# CAN-FD_Shield.net
KiCad netlist of a schematic drawn in EAGLE
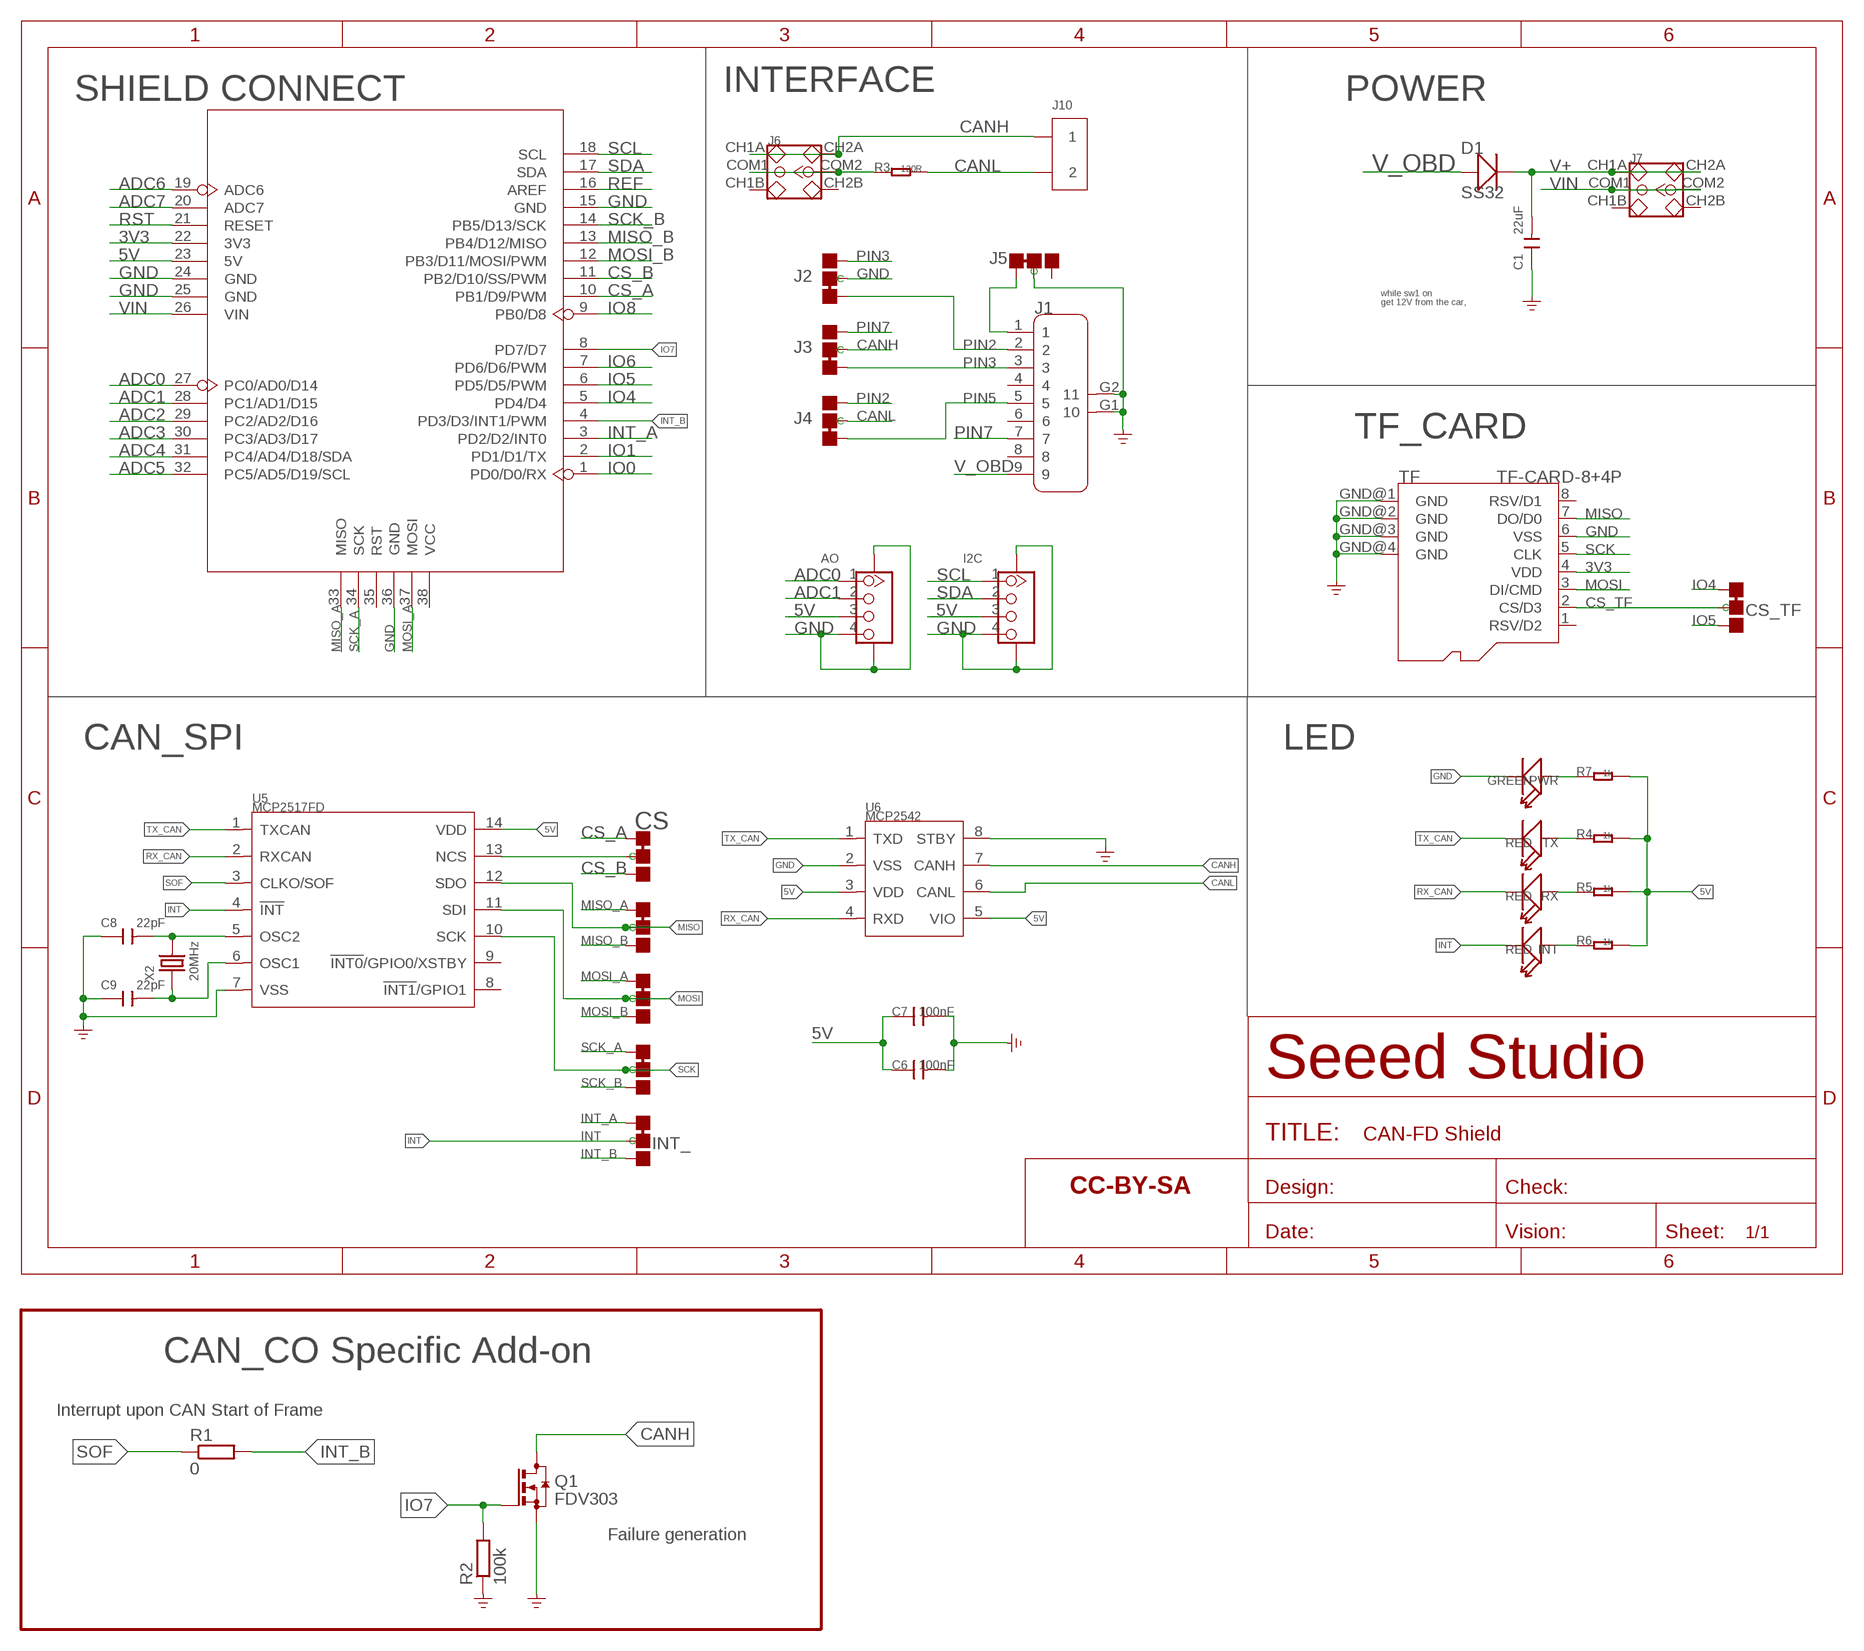
[diagram p0: schematic, sheet 1]

(export (version "E")
  (design (tool "Eeschema 10.0.6"))
  (components
    (comp (ref "AO")
      (value "GROVE-CONNECTOR-SMD'90D'")
      (footprint "eagle-import:HW4-SMD-2.0-90D")
      (libsource (lib "eagle-import") (part "GROVE-CONNECTOR-SMD'90D'"))
    )
    (comp (ref "C1")
      (value "22uF")
      (footprint "eagle-import:C1206")
      (libsource (lib "eagle-import") (part "CAP-1206"))
    )
    (comp (ref "C6")
      (value "100nF")
      (footprint "eagle-import:0603")
      (libsource (lib "eagle-import") (part "C-0603"))
    )
    (comp (ref "C7")
      (value "100nF")
      (footprint "eagle-import:0603")
      (libsource (lib "eagle-import") (part "C-0603"))
    )
    (comp (ref "C8")
      (value "22pF")
      (footprint "eagle-import:C0603")
      (libsource (lib "eagle-import") (part "CAP-0603"))
    )
    (comp (ref "C9")
      (value "22pF")
      (footprint "eagle-import:C0603")
      (libsource (lib "eagle-import") (part "CAP-0603"))
    )
    (comp (ref "CS")
      (value "JUMPER-3P-SHORT")
      (footprint "eagle-import:3P-SMD-SHORT")
      (libsource (lib "eagle-import") (part "JUMPER-3P-SHORT"))
    )
    (comp (ref "CS_TF")
      (value "JUMPER-3P-SHORT")
      (footprint "eagle-import:3P-SMD-SHORT")
      (libsource (lib "eagle-import") (part "JUMPER-3P-SHORT"))
    )
    (comp (ref "D1")
      (value "SS32")
      (footprint "eagle-import:D2010")
      (libsource (lib "eagle-import") (part "D-SMA"))
    )
    (comp (ref "I2C")
      (value "GROVE-CONNECTOR-SMD'90D'")
      (footprint "eagle-import:HW4-SMD-2.0-90D")
      (libsource (lib "eagle-import") (part "GROVE-CONNECTOR-SMD'90D'"))
    )
    (comp (ref "INT")
      (value "RED")
      (footprint "eagle-import:LED-0603")
      (libsource (lib "eagle-import") (part "LED'0603'"))
    )
    (comp (ref "INT_")
      (value "JUMPER-3P-SHORT")
      (footprint "eagle-import:3P-SMD-SHORT")
      (libsource (lib "eagle-import") (part "JUMPER-3P-SHORT"))
    )
    (comp (ref "J1")
      (value "DB9'MEAL'")
      (footprint "eagle-import:DB9-MEAL")
      (libsource (lib "eagle-import") (part "DB9'MEAL'"))
    )
    (comp (ref "J2")
      (value "JUMPER-3P-SHORT")
      (footprint "eagle-import:3P-SMD-SHORT")
      (libsource (lib "eagle-import") (part "JUMPER-3P-SHORT"))
    )
    (comp (ref "J3")
      (value "JUMPER-3P-SHORT")
      (footprint "eagle-import:3P-SMD-SHORT")
      (libsource (lib "eagle-import") (part "JUMPER-3P-SHORT"))
    )
    (comp (ref "J4")
      (value "JUMPER-3P-SHORT")
      (footprint "eagle-import:3P-SMD-SHORT")
      (libsource (lib "eagle-import") (part "JUMPER-3P-SHORT"))
    )
    (comp (ref "J5")
      (value "JUMPER-3P-SHORT")
      (footprint "eagle-import:3P-SMD-SHORT")
      (libsource (lib "eagle-import") (part "JUMPER-3P-SHORT"))
    )
    (comp (ref "J6")
      (value "SWITCH-2CH-6P")
      (footprint "eagle-import:6P-2CH-2.54-7.6X3.0")
      (libsource (lib "eagle-import") (part "SWITCH-2CH-6P"))
    )
    (comp (ref "J7")
      (value "SWITCH-2CH-6P")
      (footprint "eagle-import:6P-2CH-2.54-7.6X3.0")
      (libsource (lib "eagle-import") (part "SWITCH-2CH-6P"))
    )
    (comp (ref "J10")
      (value "SCREW-TERMINAL-2P'5.08'")
      (footprint "eagle-import:H2-5.0-10.5X8.0MM")
      (libsource (lib "eagle-import") (part "SCREW-TERMINAL-2P'5.08'"))
    )
    (comp (ref "MISO")
      (value "JUMPER-3P-SHORT")
      (footprint "eagle-import:3P-SMD-SHORT")
      (libsource (lib "eagle-import") (part "JUMPER-3P-SHORT"))
    )
    (comp (ref "MOSI")
      (value "JUMPER-3P-SHORT")
      (footprint "eagle-import:3P-SMD-SHORT")
      (libsource (lib "eagle-import") (part "JUMPER-3P-SHORT"))
    )
    (comp (ref "PWR")
      (value "GREEN")
      (footprint "eagle-import:LED-0603")
      (libsource (lib "eagle-import") (part "LED'0603'"))
    )
    (comp (ref "Q1")
      (value "FDV303")
      (footprint "eagle-import:SOT23")
      (libsource (lib "eagle-import") (part "BSS123"))
    )
    (comp (ref "R1")
      (value "0")
      (footprint "eagle-import:R0603")
      (libsource (lib "eagle-import") (part "R-EU_R0603"))
    )
    (comp (ref "R2")
      (value "100k")
      (footprint "eagle-import:R0603")
      (libsource (lib "eagle-import") (part "R-EU_R0603"))
    )
    (comp (ref "R3")
      (value "120R")
      (footprint "eagle-import:0603")
      (libsource (lib "eagle-import") (part "R-0603"))
    )
    (comp (ref "R4")
      (value "1k")
      (footprint "eagle-import:0603")
      (libsource (lib "eagle-import") (part "R-0603"))
    )
    (comp (ref "R5")
      (value "1k")
      (footprint "eagle-import:0603")
      (libsource (lib "eagle-import") (part "R-0603"))
    )
    (comp (ref "R6")
      (value "1k")
      (footprint "eagle-import:0603")
      (libsource (lib "eagle-import") (part "R-0603"))
    )
    (comp (ref "R7")
      (value "1k")
      (footprint "eagle-import:0603")
      (libsource (lib "eagle-import") (part "R-0603"))
    )
    (comp (ref "RX")
      (value "RED")
      (footprint "eagle-import:LED-0603")
      (libsource (lib "eagle-import") (part "LED'0603'"))
    )
    (comp (ref "SCK")
      (value "JUMPER-3P-SHORT")
      (footprint "eagle-import:3P-SMD-SHORT")
      (libsource (lib "eagle-import") (part "JUMPER-3P-SHORT"))
    )
    (comp (ref "TF")
      (value "TF-CARD-8+4P")
      (footprint "eagle-import:TF-8+4P-1.1-13.5X15MM")
      (libsource (lib "eagle-import") (part "TF-CARD-8+4P"))
    )
    (comp (ref "TX")
      (value "RED")
      (footprint "eagle-import:LED-0603")
      (libsource (lib "eagle-import") (part "LED'0603'"))
    )
    (comp (ref "U$5")
      (value "SEEEDSTUDIO-OPEN-SCH-FRAME")
      (footprint "eagle-import:SEEEDSTUDIO-PCB-FRAME")
      (libsource (lib "eagle-import") (part "SEEEDSTUDIO-OPEN-SCH-FRAME"))
    )
    (comp (ref "U4")
      (value "ARDUINO-38P'WITH/-SILK'")
      (footprint "eagle-import:ARDUINO-38P-WITH_-SILK-500519002")
      (libsource (lib "eagle-import") (part "ARDUINO-38P'WITH/-SILK'"))
    )
    (comp (ref "U5")
      (value "MCP2517FD")
      (footprint "eagle-import:SOIC14-1.27-8.6X3.9MM")
      (libsource (lib "eagle-import") (part "CONTROLLER-MCP2517FD"))
    )
    (comp (ref "U6")
      (value "MCP2542")
      (footprint "eagle-import:SOIC8-1.27-5X4MM")
      (libsource (lib "eagle-import") (part "TRANSCEIVER-MCP2542"))
    )
    (comp (ref "X2")
      (value "20MHz")
      (footprint "eagle-import:HC49US")
      (libsource (lib "eagle-import") (part "CRYSTAL-2P'HC49US'"))
    )
  )
  (nets
    (net (code "1") (name "/3V3") (class "Default")
      (node (ref "TF") (pin "4") (pinfunction "VDD_4") (pintype "bidirectional"))
      (node (ref "U4") (pin "22") (pinfunction "3V3_22") (pintype "bidirectional"))
    )
    (net (code "2") (name "/ADC0") (class "Default")
      (node (ref "AO") (pin "1") (pinfunction "1_1") (pintype "bidirectional"))
      (node (ref "U4") (pin "27") (pinfunction "PC0/AD0/D14_27") (pintype "bidirectional"))
    )
    (net (code "3") (name "/ADC1") (class "Default")
      (node (ref "AO") (pin "2") (pinfunction "2_2") (pintype "bidirectional"))
      (node (ref "U4") (pin "28") (pinfunction "PC1/AD1/D15_28") (pintype "bidirectional"))
    )
    (net (code "4") (name "/ADC2") (class "Default")
      (node (ref "U4") (pin "29") (pinfunction "PC2/AD2/D16_29") (pintype "bidirectional"))
    )
    (net (code "5") (name "/ADC3") (class "Default")
      (node (ref "U4") (pin "30") (pinfunction "PC3/AD3/D17_30") (pintype "bidirectional"))
    )
    (net (code "6") (name "/ADC4") (class "Default")
      (node (ref "U4") (pin "31") (pinfunction "PC4/AD4/D18/SDA_31") (pintype "bidirectional"))
    )
    (net (code "7") (name "/ADC5") (class "Default")
      (node (ref "U4") (pin "32") (pinfunction "PC5/AD5/D19/SCL_32") (pintype "bidirectional"))
    )
    (net (code "8") (name "/ADC6") (class "Default")
      (node (ref "U4") (pin "19") (pinfunction "ADC6_19") (pintype "bidirectional"))
    )
    (net (code "9") (name "/ADC7") (class "Default")
      (node (ref "U4") (pin "20") (pinfunction "ADC7_20") (pintype "bidirectional"))
    )
    (net (code "10") (name "/CS_A") (class "Default")
      (node (ref "CS") (pin "11") (pinfunction "L_11") (pintype "bidirectional"))
      (node (ref "U4") (pin "10") (pinfunction "PB1/D9/PWM_10") (pintype "bidirectional"))
    )
    (net (code "11") (name "/CS_B") (class "Default")
      (node (ref "CS") (pin "00") (pinfunction "R_00") (pintype "bidirectional"))
      (node (ref "U4") (pin "11") (pinfunction "PB2/D10/SS/PWM_11") (pintype "bidirectional"))
    )
    (net (code "12") (name "/CS_TF") (class "Default")
      (node (ref "CS_TF") (pin "MM") (pinfunction "C_MM") (pintype "bidirectional"))
      (node (ref "TF") (pin "2") (pinfunction "CS/D3_2") (pintype "bidirectional"))
    )
    (net (code "13") (name "/INT_A") (class "Default")
      (node (ref "INT_") (pin "11") (pinfunction "L_11") (pintype "bidirectional"))
      (node (ref "U4") (pin "3") (pinfunction "PD2/D2/INT0_3") (pintype "bidirectional"))
    )
    (net (code "14") (name "/IO0") (class "Default")
      (node (ref "U4") (pin "1") (pinfunction "PD0/D0/RX_1") (pintype "bidirectional"))
    )
    (net (code "15") (name "/IO1") (class "Default")
      (node (ref "U4") (pin "2") (pinfunction "PD1/D1/TX_2") (pintype "bidirectional"))
    )
    (net (code "16") (name "/IO4") (class "Default")
      (node (ref "CS_TF") (pin "11") (pinfunction "L_11") (pintype "bidirectional"))
      (node (ref "U4") (pin "5") (pinfunction "PD4/D4_5") (pintype "bidirectional"))
    )
    (net (code "17") (name "/IO5") (class "Default")
      (node (ref "CS_TF") (pin "00") (pinfunction "R_00") (pintype "bidirectional"))
      (node (ref "U4") (pin "6") (pinfunction "PD5/D5/PWM_6") (pintype "bidirectional"))
    )
    (net (code "18") (name "/IO6") (class "Default")
      (node (ref "U4") (pin "7") (pinfunction "PD6/D6/PWM_7") (pintype "bidirectional"))
    )
    (net (code "19") (name "/IO8") (class "Default")
      (node (ref "U4") (pin "9") (pinfunction "PB0/D8_9") (pintype "bidirectional"))
    )
    (net (code "20") (name "/MISO_A") (class "Default")
      (node (ref "MISO") (pin "11") (pinfunction "L_11") (pintype "bidirectional"))
      (node (ref "U4") (pin "33") (pinfunction "MISO_33") (pintype "bidirectional"))
    )
    (net (code "21") (name "/MISO_B") (class "Default")
      (node (ref "MISO") (pin "00") (pinfunction "R_00") (pintype "bidirectional"))
      (node (ref "U4") (pin "13") (pinfunction "PB4/D12/MISO_13") (pintype "bidirectional"))
    )
    (net (code "22") (name "/MOSI_A") (class "Default")
      (node (ref "MOSI") (pin "11") (pinfunction "L_11") (pintype "bidirectional"))
      (node (ref "U4") (pin "37") (pinfunction "MOSI_37") (pintype "bidirectional"))
    )
    (net (code "23") (name "/MOSI_B") (class "Default")
      (node (ref "MOSI") (pin "00") (pinfunction "R_00") (pintype "bidirectional"))
      (node (ref "U4") (pin "12") (pinfunction "PB3/D11/MOSI/PWM_12") (pintype "bidirectional"))
    )
    (net (code "24") (name "/PIN2") (class "Default")
      (node (ref "J1") (pin "2") (pinfunction "2_2") (pintype "bidirectional"))
      (node (ref "J2") (pin "11") (pinfunction "L_11") (pintype "bidirectional"))
      (node (ref "J4") (pin "00") (pinfunction "R_00") (pintype "bidirectional"))
    )
    (net (code "25") (name "/PIN3") (class "Default")
      (node (ref "J1") (pin "3") (pinfunction "3_3") (pintype "bidirectional"))
      (node (ref "J2") (pin "00") (pinfunction "R_00") (pintype "bidirectional"))
      (node (ref "J3") (pin "11") (pinfunction "L_11") (pintype "bidirectional"))
    )
    (net (code "26") (name "/PIN5") (class "Default")
      (node (ref "J1") (pin "5") (pinfunction "5_5") (pintype "bidirectional"))
      (node (ref "J4") (pin "11") (pinfunction "L_11") (pintype "bidirectional"))
    )
    (net (code "27") (name "/PIN7") (class "Default")
      (node (ref "J1") (pin "7") (pinfunction "7_7") (pintype "bidirectional"))
      (node (ref "J3") (pin "00") (pinfunction "R_00") (pintype "bidirectional"))
    )
    (net (code "28") (name "/REF") (class "Default")
      (node (ref "U4") (pin "16") (pinfunction "AREF_16") (pintype "bidirectional"))
    )
    (net (code "29") (name "/RST") (class "Default")
      (node (ref "U4") (pin "21") (pinfunction "RESET_21") (pintype "bidirectional"))
    )
    (net (code "30") (name "/SCK_A") (class "Default")
      (node (ref "SCK") (pin "11") (pinfunction "L_11") (pintype "bidirectional"))
      (node (ref "U4") (pin "34") (pinfunction "SCK_34") (pintype "bidirectional"))
    )
    (net (code "31") (name "/SCK_B") (class "Default")
      (node (ref "SCK") (pin "00") (pinfunction "R_00") (pintype "bidirectional"))
      (node (ref "U4") (pin "14") (pinfunction "PB5/D13/SCK_14") (pintype "bidirectional"))
    )
    (net (code "32") (name "/SCL") (class "Default")
      (node (ref "I2C") (pin "1") (pinfunction "1_1") (pintype "bidirectional"))
      (node (ref "U4") (pin "18") (pinfunction "SCL_18") (pintype "bidirectional"))
    )
    (net (code "33") (name "/SDA") (class "Default")
      (node (ref "I2C") (pin "2") (pinfunction "2_2") (pintype "bidirectional"))
      (node (ref "U4") (pin "17") (pinfunction "SDA_17") (pintype "bidirectional"))
    )
    (net (code "34") (name "/V+") (class "Default")
      (node (ref "C1") (pin "2") (pinfunction "2_2") (pintype "passive"))
      (node (ref "D1") (pin "-") (pinfunction "-_-") (pintype "passive"))
      (node (ref "J7") (pin "CH1A") (pinfunction "CH1A_CH1A") (pintype "bidirectional"))
      (node (ref "J7") (pin "CH2A") (pinfunction "CH2A_CH2A") (pintype "bidirectional"))
    )
    (net (code "35") (name "/VIN") (class "Default")
      (node (ref "J7") (pin "COM1") (pinfunction "COM1_COM1") (pintype "bidirectional"))
      (node (ref "J7") (pin "COM2") (pinfunction "COM2_COM2") (pintype "bidirectional"))
      (node (ref "U4") (pin "26") (pinfunction "VIN_26") (pintype "bidirectional"))
    )
    (net (code "36") (name "/V_OBD") (class "Default")
      (node (ref "D1") (pin "+") (pinfunction "+_+") (pintype "passive"))
      (node (ref "J1") (pin "9") (pinfunction "9_9") (pintype "bidirectional"))
    )
    (net (code "37") (name "5V") (class "Default")
      (node (ref "AO") (pin "3") (pinfunction "3_3") (pintype "bidirectional"))
      (node (ref "C6") (pin "1") (pinfunction "1_1") (pintype "passive"))
      (node (ref "C7") (pin "1") (pinfunction "1_1") (pintype "passive"))
      (node (ref "I2C") (pin "3") (pinfunction "3_3") (pintype "bidirectional"))
      (node (ref "R4") (pin "2") (pinfunction "2_2") (pintype "passive"))
      (node (ref "R5") (pin "2") (pinfunction "2_2") (pintype "passive"))
      (node (ref "R6") (pin "2") (pinfunction "2_2") (pintype "passive"))
      (node (ref "R7") (pin "2") (pinfunction "2_2") (pintype "passive"))
      (node (ref "U4") (pin "23") (pinfunction "5V_23") (pintype "bidirectional"))
      (node (ref "U5") (pin "14") (pinfunction "VDD_14") (pintype "bidirectional"))
      (node (ref "U6") (pin "3") (pinfunction "VDD_3") (pintype "bidirectional"))
      (node (ref "U6") (pin "5") (pinfunction "VIO_5") (pintype "bidirectional"))
    )
    (net (code "38") (name "CANH") (class "Default")
      (node (ref "J10") (pin "1") (pinfunction "1_1") (pintype "bidirectional"))
      (node (ref "J3") (pin "MM") (pinfunction "C_MM") (pintype "bidirectional"))
      (node (ref "J6") (pin "CH1A") (pinfunction "CH1A_CH1A") (pintype "bidirectional"))
      (node (ref "J6") (pin "CH2A") (pinfunction "CH2A_CH2A") (pintype "bidirectional"))
      (node (ref "Q1") (pin "3") (pinfunction "D_3") (pintype "passive"))
      (node (ref "U6") (pin "7") (pinfunction "CANH_7") (pintype "bidirectional"))
    )
    (net (code "39") (name "CANL") (class "Default")
      (node (ref "J10") (pin "2") (pinfunction "2_2") (pintype "bidirectional"))
      (node (ref "J4") (pin "MM") (pinfunction "C_MM") (pintype "bidirectional"))
      (node (ref "R3") (pin "2") (pinfunction "2_2") (pintype "passive"))
      (node (ref "U6") (pin "6") (pinfunction "CANL_6") (pintype "bidirectional"))
    )
    (net (code "40") (name "GND") (class "Default")
      (node (ref "AO") (pin "4") (pinfunction "4_4") (pintype "bidirectional"))
      (node (ref "AO") (pin "SS1") (pinfunction "SS1_SS1") (pintype "bidirectional"))
      (node (ref "AO") (pin "SS2") (pinfunction "SS2_SS2") (pintype "bidirectional"))
      (node (ref "C1") (pin "1") (pinfunction "1_1") (pintype "passive"))
      (node (ref "C6") (pin "2") (pinfunction "2_2") (pintype "passive"))
      (node (ref "C7") (pin "2") (pinfunction "2_2") (pintype "passive"))
      (node (ref "C8") (pin "1") (pinfunction "1_1") (pintype "passive"))
      (node (ref "C9") (pin "1") (pinfunction "1_1") (pintype "passive"))
      (node (ref "I2C") (pin "4") (pinfunction "4_4") (pintype "bidirectional"))
      (node (ref "I2C") (pin "SS1") (pinfunction "SS1_SS1") (pintype "bidirectional"))
      (node (ref "I2C") (pin "SS2") (pinfunction "SS2_SS2") (pintype "bidirectional"))
      (node (ref "J1") (pin "G1") (pinfunction "10_G1") (pintype "bidirectional"))
      (node (ref "J1") (pin "G2") (pinfunction "11_G2") (pintype "bidirectional"))
      (node (ref "J2") (pin "MM") (pinfunction "C_MM") (pintype "bidirectional"))
      (node (ref "J5") (pin "MM") (pinfunction "C_MM") (pintype "bidirectional"))
      (node (ref "PWR") (pin "-") (pinfunction "-_-") (pintype "passive"))
      (node (ref "Q1") (pin "2") (pinfunction "S_2") (pintype "passive"))
      (node (ref "R2") (pin "1") (pinfunction "1_1") (pintype "passive"))
      (node (ref "TF") (pin "6") (pinfunction "VSS_6") (pintype "bidirectional"))
      (node (ref "TF") (pin "GND@1") (pinfunction "GND_GND@1") (pintype "bidirectional"))
      (node (ref "TF") (pin "GND@2") (pinfunction "GND_GND@2") (pintype "bidirectional"))
      (node (ref "TF") (pin "GND@3") (pinfunction "GND_GND@3") (pintype "bidirectional"))
      (node (ref "TF") (pin "GND@4") (pinfunction "GND_GND@4") (pintype "bidirectional"))
      (node (ref "U4") (pin "15") (pinfunction "GND_15") (pintype "bidirectional"))
      (node (ref "U4") (pin "24") (pinfunction "GND_24") (pintype "bidirectional"))
      (node (ref "U4") (pin "25") (pinfunction "GND_25") (pintype "bidirectional"))
      (node (ref "U4") (pin "36") (pinfunction "GND_36") (pintype "bidirectional"))
      (node (ref "U5") (pin "7") (pinfunction "VSS_7") (pintype "bidirectional"))
      (node (ref "U6") (pin "2") (pinfunction "VSS_2") (pintype "bidirectional"))
      (node (ref "U6") (pin "8") (pinfunction "STBY_8") (pintype "bidirectional"))
    )
    (net (code "41") (name "INT") (class "Default")
      (node (ref "INT") (pin "-") (pinfunction "-_-") (pintype "passive"))
      (node (ref "INT_") (pin "MM") (pinfunction "C_MM") (pintype "bidirectional"))
      (node (ref "U5") (pin "4") (pinfunction "~{INT}_4") (pintype "bidirectional"))
    )
    (net (code "42") (name "INT_B") (class "Default")
      (node (ref "INT_") (pin "00") (pinfunction "R_00") (pintype "bidirectional"))
      (node (ref "R1") (pin "2") (pinfunction "2_2") (pintype "passive"))
      (node (ref "U4") (pin "4") (pinfunction "PD3/D3/INT1/PWM_4") (pintype "bidirectional"))
    )
    (net (code "43") (name "IO7") (class "Default")
      (node (ref "Q1") (pin "1") (pinfunction "G_1") (pintype "passive"))
      (node (ref "R2") (pin "2") (pinfunction "2_2") (pintype "passive"))
      (node (ref "U4") (pin "8") (pinfunction "PD7/D7_8") (pintype "bidirectional"))
    )
    (net (code "44") (name "MISO") (class "Default")
      (node (ref "MISO") (pin "MM") (pinfunction "C_MM") (pintype "bidirectional"))
      (node (ref "TF") (pin "7") (pinfunction "DO/D0_7") (pintype "bidirectional"))
      (node (ref "U5") (pin "12") (pinfunction "SDO_12") (pintype "bidirectional"))
    )
    (net (code "45") (name "MOSI") (class "Default")
      (node (ref "MOSI") (pin "MM") (pinfunction "C_MM") (pintype "bidirectional"))
      (node (ref "TF") (pin "3") (pinfunction "DI/CMD_3") (pintype "bidirectional"))
      (node (ref "U5") (pin "11") (pinfunction "SDI_11") (pintype "bidirectional"))
    )
    (net (code "46") (name "Net-(CS-C)") (class "Default")
      (node (ref "CS") (pin "MM") (pinfunction "C_MM") (pintype "bidirectional"))
      (node (ref "U5") (pin "13") (pinfunction "NCS_13") (pintype "bidirectional"))
    )
    (net (code "47") (name "Net-(INT-Pad+)") (class "Default")
      (node (ref "INT") (pin "+") (pinfunction "+_+") (pintype "passive"))
      (node (ref "R6") (pin "1") (pinfunction "1_1") (pintype "passive"))
    )
    (net (code "48") (name "Net-(J5-L)") (class "Default")
      (node (ref "J1") (pin "1") (pinfunction "1_1") (pintype "bidirectional"))
      (node (ref "J5") (pin "11") (pinfunction "L_11") (pintype "bidirectional"))
    )
    (net (code "49") (name "Net-(J6-PadCOM1)") (class "Default")
      (node (ref "J6") (pin "COM1") (pinfunction "COM1_COM1") (pintype "bidirectional"))
      (node (ref "J6") (pin "COM2") (pinfunction "COM2_COM2") (pintype "bidirectional"))
      (node (ref "R3") (pin "1") (pinfunction "1_1") (pintype "passive"))
    )
    (net (code "50") (name "Net-(PWR-Pad+)") (class "Default")
      (node (ref "PWR") (pin "+") (pinfunction "+_+") (pintype "passive"))
      (node (ref "R7") (pin "1") (pinfunction "1_1") (pintype "passive"))
    )
    (net (code "51") (name "Net-(R4-Pad1)") (class "Default")
      (node (ref "R4") (pin "1") (pinfunction "1_1") (pintype "passive"))
      (node (ref "TX") (pin "+") (pinfunction "+_+") (pintype "passive"))
    )
    (net (code "52") (name "Net-(R5-Pad1)") (class "Default")
      (node (ref "R5") (pin "1") (pinfunction "1_1") (pintype "passive"))
      (node (ref "RX") (pin "+") (pinfunction "+_+") (pintype "passive"))
    )
    (net (code "53") (name "Net-(U5-OSC1)") (class "Default")
      (node (ref "C9") (pin "2") (pinfunction "2_2") (pintype "passive"))
      (node (ref "U5") (pin "6") (pinfunction "OSC1_6") (pintype "bidirectional"))
      (node (ref "X2") (pin "1") (pinfunction "1_1") (pintype "passive"))
    )
    (net (code "54") (name "Net-(U5-OSC2)") (class "Default")
      (node (ref "C8") (pin "2") (pinfunction "2_2") (pintype "passive"))
      (node (ref "U5") (pin "5") (pinfunction "OSC2_5") (pintype "bidirectional"))
      (node (ref "X2") (pin "2") (pinfunction "2_2") (pintype "passive"))
    )
    (net (code "55") (name "RX_CAN") (class "Default")
      (node (ref "RX") (pin "-") (pinfunction "-_-") (pintype "passive"))
      (node (ref "U5") (pin "2") (pinfunction "RXCAN_2") (pintype "bidirectional"))
      (node (ref "U6") (pin "4") (pinfunction "RXD_4") (pintype "bidirectional"))
    )
    (net (code "56") (name "SCK") (class "Default")
      (node (ref "SCK") (pin "MM") (pinfunction "C_MM") (pintype "bidirectional"))
      (node (ref "TF") (pin "5") (pinfunction "CLK_5") (pintype "bidirectional"))
      (node (ref "U5") (pin "10") (pinfunction "SCK_10") (pintype "bidirectional"))
    )
    (net (code "57") (name "SOF") (class "Default")
      (node (ref "R1") (pin "1") (pinfunction "1_1") (pintype "passive"))
      (node (ref "U5") (pin "3") (pinfunction "CLKO/SOF_3") (pintype "bidirectional"))
    )
    (net (code "58") (name "TX_CAN") (class "Default")
      (node (ref "TX") (pin "-") (pinfunction "-_-") (pintype "passive"))
      (node (ref "U5") (pin "1") (pinfunction "TXCAN_1") (pintype "bidirectional"))
      (node (ref "U6") (pin "1") (pinfunction "TXD_1") (pintype "bidirectional"))
    )
    (net (code "59") (name "unconnected-(J1-Pad4)") (class "Default")
      (node (ref "J1") (pin "4") (pinfunction "4_4") (pintype "bidirectional"))
    )
    (net (code "60") (name "unconnected-(J1-Pad6)") (class "Default")
      (node (ref "J1") (pin "6") (pinfunction "6_6") (pintype "bidirectional"))
    )
    (net (code "61") (name "unconnected-(J1-Pad8)") (class "Default")
      (node (ref "J1") (pin "8") (pinfunction "8_8") (pintype "bidirectional"))
    )
    (net (code "62") (name "unconnected-(J5-R-Pad00)") (class "Default")
      (node (ref "J5") (pin "00") (pinfunction "R_00") (pintype "bidirectional"))
    )
    (net (code "63") (name "unconnected-(J6-PadCH1B)") (class "Default")
      (node (ref "J6") (pin "CH1B") (pinfunction "CH1B_CH1B") (pintype "bidirectional"))
    )
    (net (code "64") (name "unconnected-(J6-PadCH2B)") (class "Default")
      (node (ref "J6") (pin "CH2B") (pinfunction "CH2B_CH2B") (pintype "bidirectional"))
    )
    (net (code "65") (name "unconnected-(J7-PadCH1B)") (class "Default")
      (node (ref "J7") (pin "CH1B") (pinfunction "CH1B_CH1B") (pintype "bidirectional"))
    )
    (net (code "66") (name "unconnected-(J7-PadCH2B)") (class "Default")
      (node (ref "J7") (pin "CH2B") (pinfunction "CH2B_CH2B") (pintype "bidirectional"))
    )
    (net (code "67") (name "unconnected-(TF-RSV{slash}D1-Pad8)") (class "Default")
      (node (ref "TF") (pin "8") (pinfunction "RSV/D1_8") (pintype "bidirectional"))
    )
    (net (code "68") (name "unconnected-(TF-RSV{slash}D2-Pad1)") (class "Default")
      (node (ref "TF") (pin "1") (pinfunction "RSV/D2_1") (pintype "bidirectional"))
    )
    (net (code "69") (name "unconnected-(U4-RST-Pad35)") (class "Default")
      (node (ref "U4") (pin "35") (pinfunction "RST_35") (pintype "bidirectional"))
    )
    (net (code "70") (name "unconnected-(U4-VCC-Pad38)") (class "Default")
      (node (ref "U4") (pin "38") (pinfunction "VCC_38") (pintype "bidirectional"))
    )
    (net (code "71") (name "unconnected-(U5-~{INT0}{slash}GPIO0{slash}XSTBY-Pad9)") (class "Default")
      (node (ref "U5") (pin "9") (pinfunction "~{INT0}/GPIO0/XSTBY_9") (pintype "bidirectional"))
    )
    (net (code "72") (name "unconnected-(U5-~{INT1}{slash}GPIO1-Pad8)") (class "Default")
      (node (ref "U5") (pin "8") (pinfunction "~{INT1}/GPIO1_8") (pintype "bidirectional"))
    )
  )
)
